# senseye-2.net
KiCad netlist of a schematic drawn in EAGLE
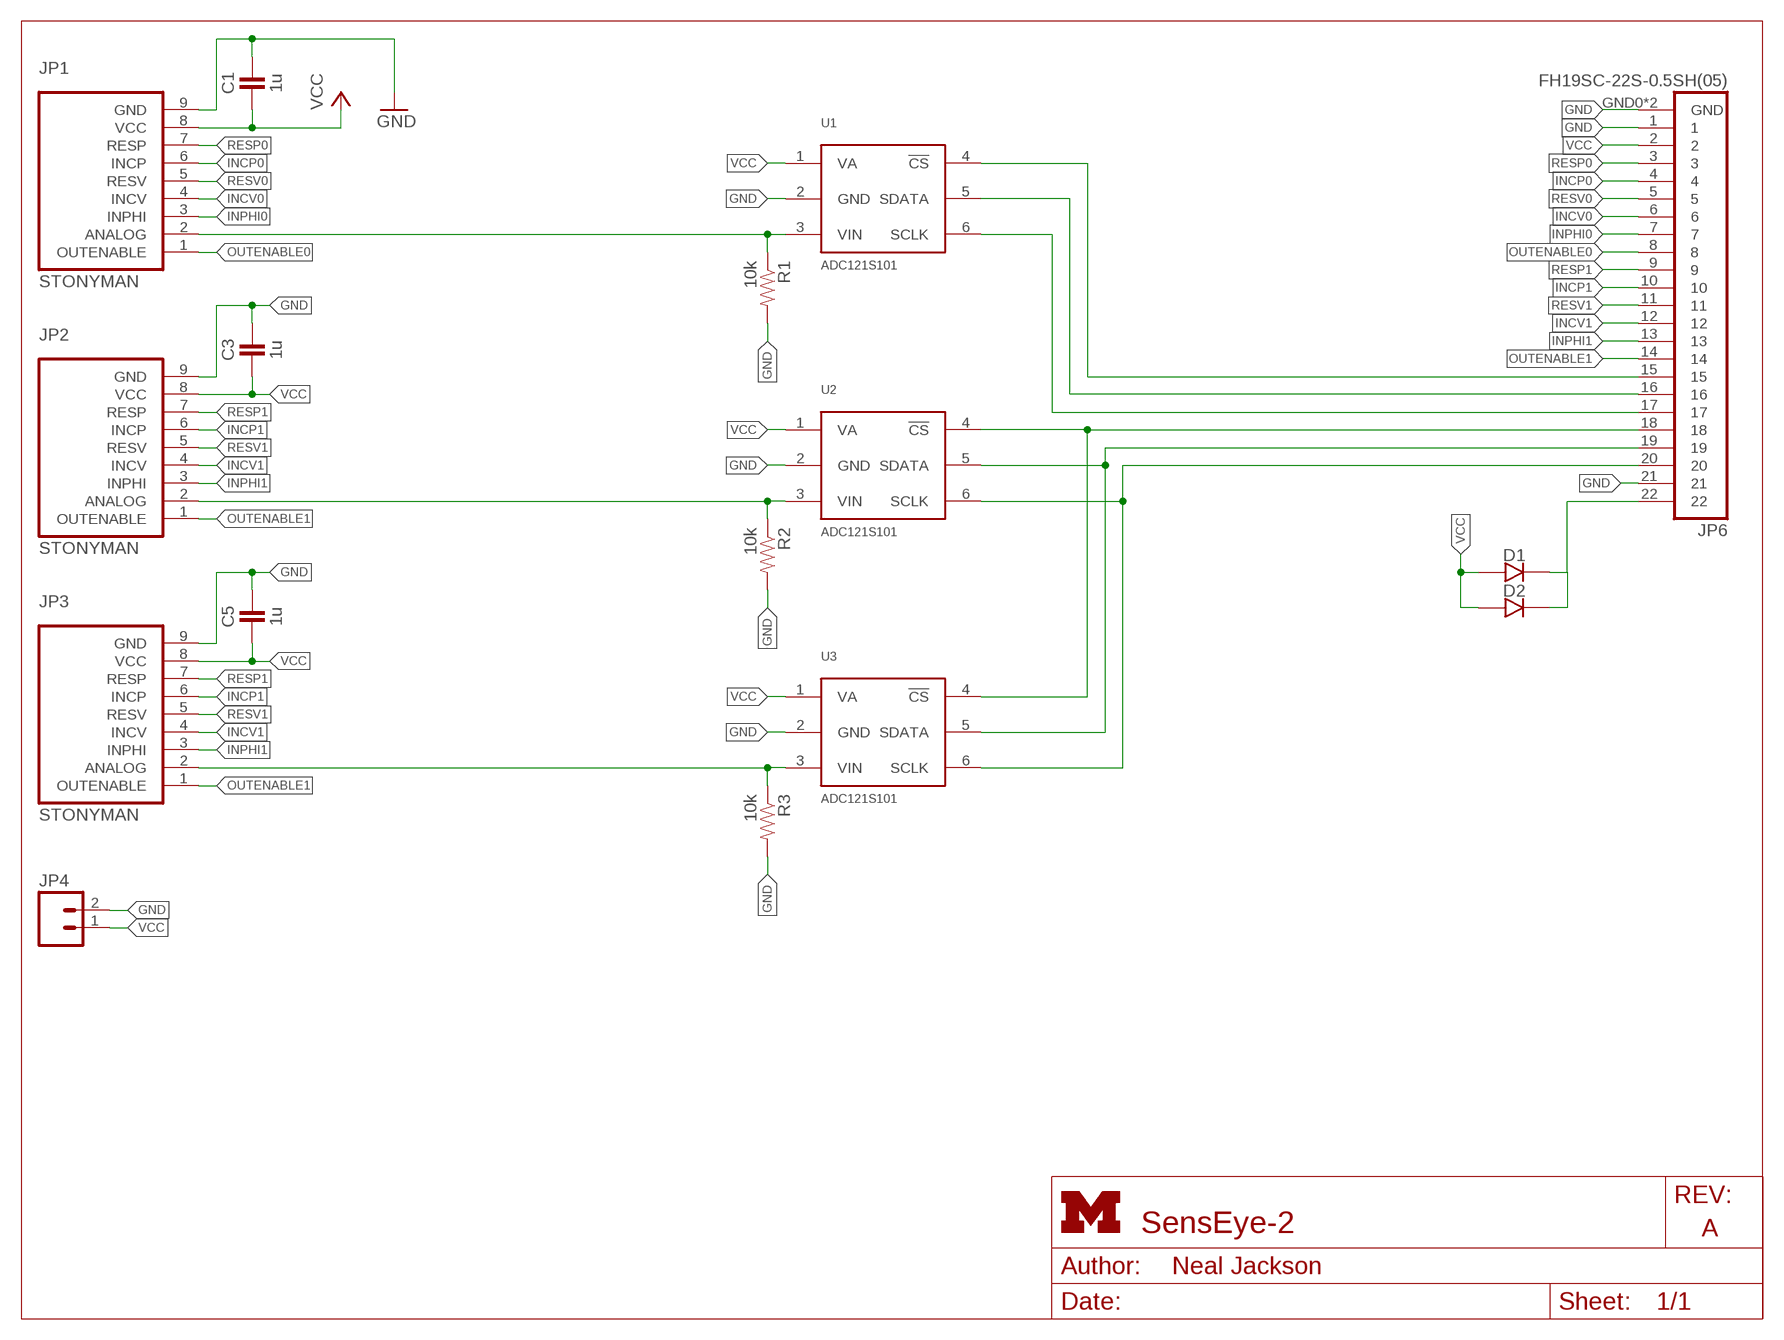
[diagram p0: schematic, sheet 1]

(export (version "E")
  (design (tool "Eeschema 10.0.6"))
  (components
    (comp (ref "C1")
      (value "1u")
      (footprint "eagle-import:0402_CAP")
      (libsource (lib "eagle-import") (part "CAPACITOR"))
    )
    (comp (ref "C3")
      (value "1u")
      (footprint "eagle-import:0402_CAP")
      (libsource (lib "eagle-import") (part "CAPACITOR"))
    )
    (comp (ref "C5")
      (value "1u")
      (footprint "eagle-import:0402_CAP")
      (libsource (lib "eagle-import") (part "CAPACITOR"))
    )
    (comp (ref "D1")
      (value "DIODE0603")
      (footprint "eagle-import:0603-DIODE")
      (libsource (lib "eagle-import") (part "DIODE0603"))
    )
    (comp (ref "D2")
      (value "DIODE0603")
      (footprint "eagle-import:0603-DIODE")
      (libsource (lib "eagle-import") (part "DIODE0603"))
    )
    (comp (ref "JP1")
      (value "STONYMAN")
      (footprint "eagle-import:1X09")
      (libsource (lib "eagle-import") (part "STONYMAN"))
    )
    (comp (ref "JP2")
      (value "STONYMAN")
      (footprint "eagle-import:1X09")
      (libsource (lib "eagle-import") (part "STONYMAN"))
    )
    (comp (ref "JP3")
      (value "STONYMAN")
      (footprint "eagle-import:1X09")
      (libsource (lib "eagle-import") (part "STONYMAN"))
    )
    (comp (ref "JP4")
      (value "M02PTH")
      (footprint "eagle-import:1X02")
      (libsource (lib "eagle-import") (part "M02PTH"))
    )
    (comp (ref "JP6")
      (value "FH19SC-22S-0.5SH(05)")
      (footprint "eagle-import:FH19SC-22S-0.5SH(05)")
      (libsource (lib "eagle-import") (part "FH19SC-22S-0.5SH(05)"))
    )
    (comp (ref "R1")
      (value "10k")
      (footprint "eagle-import:0402_RES")
      (libsource (lib "eagle-import") (part "RESISTOR0402_RES"))
    )
    (comp (ref "R2")
      (value "10k")
      (footprint "eagle-import:0402_RES")
      (libsource (lib "eagle-import") (part "RESISTOR0402_RES"))
    )
    (comp (ref "R3")
      (value "10k")
      (footprint "eagle-import:0402_RES")
      (libsource (lib "eagle-import") (part "RESISTOR0402_RES"))
    )
    (comp (ref "U1")
      (value "ADC121S101")
      (footprint "eagle-import:SOT-23-6")
      (libsource (lib "eagle-import") (part "ADC121S101"))
    )
    (comp (ref "U2")
      (value "ADC121S101")
      (footprint "eagle-import:SOT-23-6")
      (libsource (lib "eagle-import") (part "ADC121S101"))
    )
    (comp (ref "U3")
      (value "ADC121S101")
      (footprint "eagle-import:SOT-23-6")
      (libsource (lib "eagle-import") (part "ADC121S101"))
    )
  )
  (nets
    (net (code "1") (name "GND") (class "Default")
      (node (ref "C1") (pin "1") (pinfunction "1_1") (pintype "bidirectional"))
      (node (ref "C3") (pin "1") (pinfunction "1_1") (pintype "bidirectional"))
      (node (ref "C5") (pin "1") (pinfunction "1_1") (pintype "bidirectional"))
      (node (ref "JP1") (pin "9") (pinfunction "GND_9") (pintype "passive"))
      (node (ref "JP2") (pin "9") (pinfunction "GND_9") (pintype "passive"))
      (node (ref "JP3") (pin "9") (pinfunction "GND_9") (pintype "passive"))
      (node (ref "JP4") (pin "2") (pinfunction "2_2") (pintype "passive"))
      (node (ref "JP6") (pin "1") (pinfunction "1_1") (pintype "passive"))
      (node (ref "JP6") (pin "21") (pinfunction "21_21") (pintype "passive"))
      (node (ref "JP6") (pin "GND0") (pinfunction "GND_GND0") (pintype "bidirectional"))
      (node (ref "JP6") (pin "GND1") (pinfunction "GND_GND1") (pintype "bidirectional"))
      (node (ref "R1") (pin "2") (pinfunction "2_2") (pintype "passive"))
      (node (ref "R2") (pin "2") (pinfunction "2_2") (pintype "passive"))
      (node (ref "R3") (pin "2") (pinfunction "2_2") (pintype "passive"))
      (node (ref "U1") (pin "2") (pinfunction "GND_2") (pintype "bidirectional"))
      (node (ref "U2") (pin "2") (pinfunction "GND_2") (pintype "bidirectional"))
      (node (ref "U3") (pin "2") (pinfunction "GND_2") (pintype "bidirectional"))
    )
    (net (code "2") (name "INCP0") (class "Default")
      (node (ref "JP1") (pin "6") (pinfunction "INCP_6") (pintype "passive"))
      (node (ref "JP6") (pin "4") (pinfunction "4_4") (pintype "passive"))
    )
    (net (code "3") (name "INCP1") (class "Default")
      (node (ref "JP2") (pin "6") (pinfunction "INCP_6") (pintype "passive"))
      (node (ref "JP3") (pin "6") (pinfunction "INCP_6") (pintype "passive"))
      (node (ref "JP6") (pin "10") (pinfunction "10_10") (pintype "passive"))
    )
    (net (code "4") (name "INCV0") (class "Default")
      (node (ref "JP1") (pin "4") (pinfunction "INCV_4") (pintype "passive"))
      (node (ref "JP6") (pin "6") (pinfunction "6_6") (pintype "passive"))
    )
    (net (code "5") (name "INCV1") (class "Default")
      (node (ref "JP2") (pin "4") (pinfunction "INCV_4") (pintype "passive"))
      (node (ref "JP3") (pin "4") (pinfunction "INCV_4") (pintype "passive"))
      (node (ref "JP6") (pin "12") (pinfunction "12_12") (pintype "passive"))
    )
    (net (code "6") (name "INPHI0") (class "Default")
      (node (ref "JP1") (pin "3") (pinfunction "INPHI_3") (pintype "passive"))
      (node (ref "JP6") (pin "7") (pinfunction "7_7") (pintype "passive"))
    )
    (net (code "7") (name "INPHI1") (class "Default")
      (node (ref "JP2") (pin "3") (pinfunction "INPHI_3") (pintype "passive"))
      (node (ref "JP3") (pin "3") (pinfunction "INPHI_3") (pintype "passive"))
      (node (ref "JP6") (pin "13") (pinfunction "13_13") (pintype "passive"))
    )
    (net (code "8") (name "Net-(D1-CATHODE)") (class "Default")
      (node (ref "D1") (pin "2") (pinfunction "CATHODE_2") (pintype "bidirectional"))
      (node (ref "D2") (pin "2") (pinfunction "CATHODE_2") (pintype "bidirectional"))
      (node (ref "JP6") (pin "22") (pinfunction "22_22") (pintype "passive"))
    )
    (net (code "9") (name "Net-(JP1-ANALOG)") (class "Default")
      (node (ref "JP1") (pin "2") (pinfunction "ANALOG_2") (pintype "passive"))
      (node (ref "R1") (pin "1") (pinfunction "1_1") (pintype "passive"))
      (node (ref "U1") (pin "3") (pinfunction "VIN_3") (pintype "bidirectional"))
    )
    (net (code "10") (name "Net-(JP2-ANALOG)") (class "Default")
      (node (ref "JP2") (pin "2") (pinfunction "ANALOG_2") (pintype "passive"))
      (node (ref "R2") (pin "1") (pinfunction "1_1") (pintype "passive"))
      (node (ref "U2") (pin "3") (pinfunction "VIN_3") (pintype "bidirectional"))
    )
    (net (code "11") (name "Net-(JP3-ANALOG)") (class "Default")
      (node (ref "JP3") (pin "2") (pinfunction "ANALOG_2") (pintype "passive"))
      (node (ref "R3") (pin "1") (pinfunction "1_1") (pintype "passive"))
      (node (ref "U3") (pin "3") (pinfunction "VIN_3") (pintype "bidirectional"))
    )
    (net (code "12") (name "Net-(U1-SCLK)") (class "Default")
      (node (ref "JP6") (pin "17") (pinfunction "17_17") (pintype "passive"))
      (node (ref "U1") (pin "6") (pinfunction "SCLK_6") (pintype "bidirectional"))
    )
    (net (code "13") (name "Net-(U1-SDATA)") (class "Default")
      (node (ref "JP6") (pin "16") (pinfunction "16_16") (pintype "passive"))
      (node (ref "U1") (pin "5") (pinfunction "SDATA_5") (pintype "bidirectional"))
    )
    (net (code "14") (name "Net-(U1-~{CS})") (class "Default")
      (node (ref "JP6") (pin "15") (pinfunction "15_15") (pintype "passive"))
      (node (ref "U1") (pin "4") (pinfunction "~{CS}_4") (pintype "bidirectional"))
    )
    (net (code "15") (name "Net-(U2-SCLK)") (class "Default")
      (node (ref "JP6") (pin "20") (pinfunction "20_20") (pintype "passive"))
      (node (ref "U2") (pin "6") (pinfunction "SCLK_6") (pintype "bidirectional"))
      (node (ref "U3") (pin "6") (pinfunction "SCLK_6") (pintype "bidirectional"))
    )
    (net (code "16") (name "Net-(U2-SDATA)") (class "Default")
      (node (ref "JP6") (pin "19") (pinfunction "19_19") (pintype "passive"))
      (node (ref "U2") (pin "5") (pinfunction "SDATA_5") (pintype "bidirectional"))
      (node (ref "U3") (pin "5") (pinfunction "SDATA_5") (pintype "bidirectional"))
    )
    (net (code "17") (name "Net-(U2-~{CS})") (class "Default")
      (node (ref "JP6") (pin "18") (pinfunction "18_18") (pintype "passive"))
      (node (ref "U2") (pin "4") (pinfunction "~{CS}_4") (pintype "bidirectional"))
      (node (ref "U3") (pin "4") (pinfunction "~{CS}_4") (pintype "bidirectional"))
    )
    (net (code "18") (name "OUTENABLE0") (class "Default")
      (node (ref "JP1") (pin "1") (pinfunction "OUTENABLE_1") (pintype "passive"))
      (node (ref "JP6") (pin "8") (pinfunction "8_8") (pintype "passive"))
    )
    (net (code "19") (name "OUTENABLE1") (class "Default")
      (node (ref "JP2") (pin "1") (pinfunction "OUTENABLE_1") (pintype "passive"))
      (node (ref "JP3") (pin "1") (pinfunction "OUTENABLE_1") (pintype "passive"))
      (node (ref "JP6") (pin "14") (pinfunction "14_14") (pintype "passive"))
    )
    (net (code "20") (name "RESP0") (class "Default")
      (node (ref "JP1") (pin "7") (pinfunction "RESP_7") (pintype "passive"))
      (node (ref "JP6") (pin "3") (pinfunction "3_3") (pintype "passive"))
    )
    (net (code "21") (name "RESP1") (class "Default")
      (node (ref "JP2") (pin "7") (pinfunction "RESP_7") (pintype "passive"))
      (node (ref "JP3") (pin "7") (pinfunction "RESP_7") (pintype "passive"))
      (node (ref "JP6") (pin "9") (pinfunction "9_9") (pintype "passive"))
    )
    (net (code "22") (name "RESV0") (class "Default")
      (node (ref "JP1") (pin "5") (pinfunction "RESV_5") (pintype "passive"))
      (node (ref "JP6") (pin "5") (pinfunction "5_5") (pintype "passive"))
    )
    (net (code "23") (name "RESV1") (class "Default")
      (node (ref "JP2") (pin "5") (pinfunction "RESV_5") (pintype "passive"))
      (node (ref "JP3") (pin "5") (pinfunction "RESV_5") (pintype "passive"))
      (node (ref "JP6") (pin "11") (pinfunction "11_11") (pintype "passive"))
    )
    (net (code "24") (name "VCC") (class "Default")
      (node (ref "C1") (pin "2") (pinfunction "2_2") (pintype "bidirectional"))
      (node (ref "C3") (pin "2") (pinfunction "2_2") (pintype "bidirectional"))
      (node (ref "C5") (pin "2") (pinfunction "2_2") (pintype "bidirectional"))
      (node (ref "D1") (pin "1") (pinfunction "ANODE_1") (pintype "bidirectional"))
      (node (ref "D2") (pin "1") (pinfunction "ANODE_1") (pintype "bidirectional"))
      (node (ref "JP1") (pin "8") (pinfunction "VCC_8") (pintype "passive"))
      (node (ref "JP2") (pin "8") (pinfunction "VCC_8") (pintype "passive"))
      (node (ref "JP3") (pin "8") (pinfunction "VCC_8") (pintype "passive"))
      (node (ref "JP4") (pin "1") (pinfunction "1_1") (pintype "passive"))
      (node (ref "JP6") (pin "2") (pinfunction "2_2") (pintype "passive"))
      (node (ref "U1") (pin "1") (pinfunction "VA_1") (pintype "bidirectional"))
      (node (ref "U2") (pin "1") (pinfunction "VA_1") (pintype "bidirectional"))
      (node (ref "U3") (pin "1") (pinfunction "VA_1") (pintype "bidirectional"))
    )
  )
)
